# rgb_driver.net
KiCad netlist of a schematic drawn in EAGLE
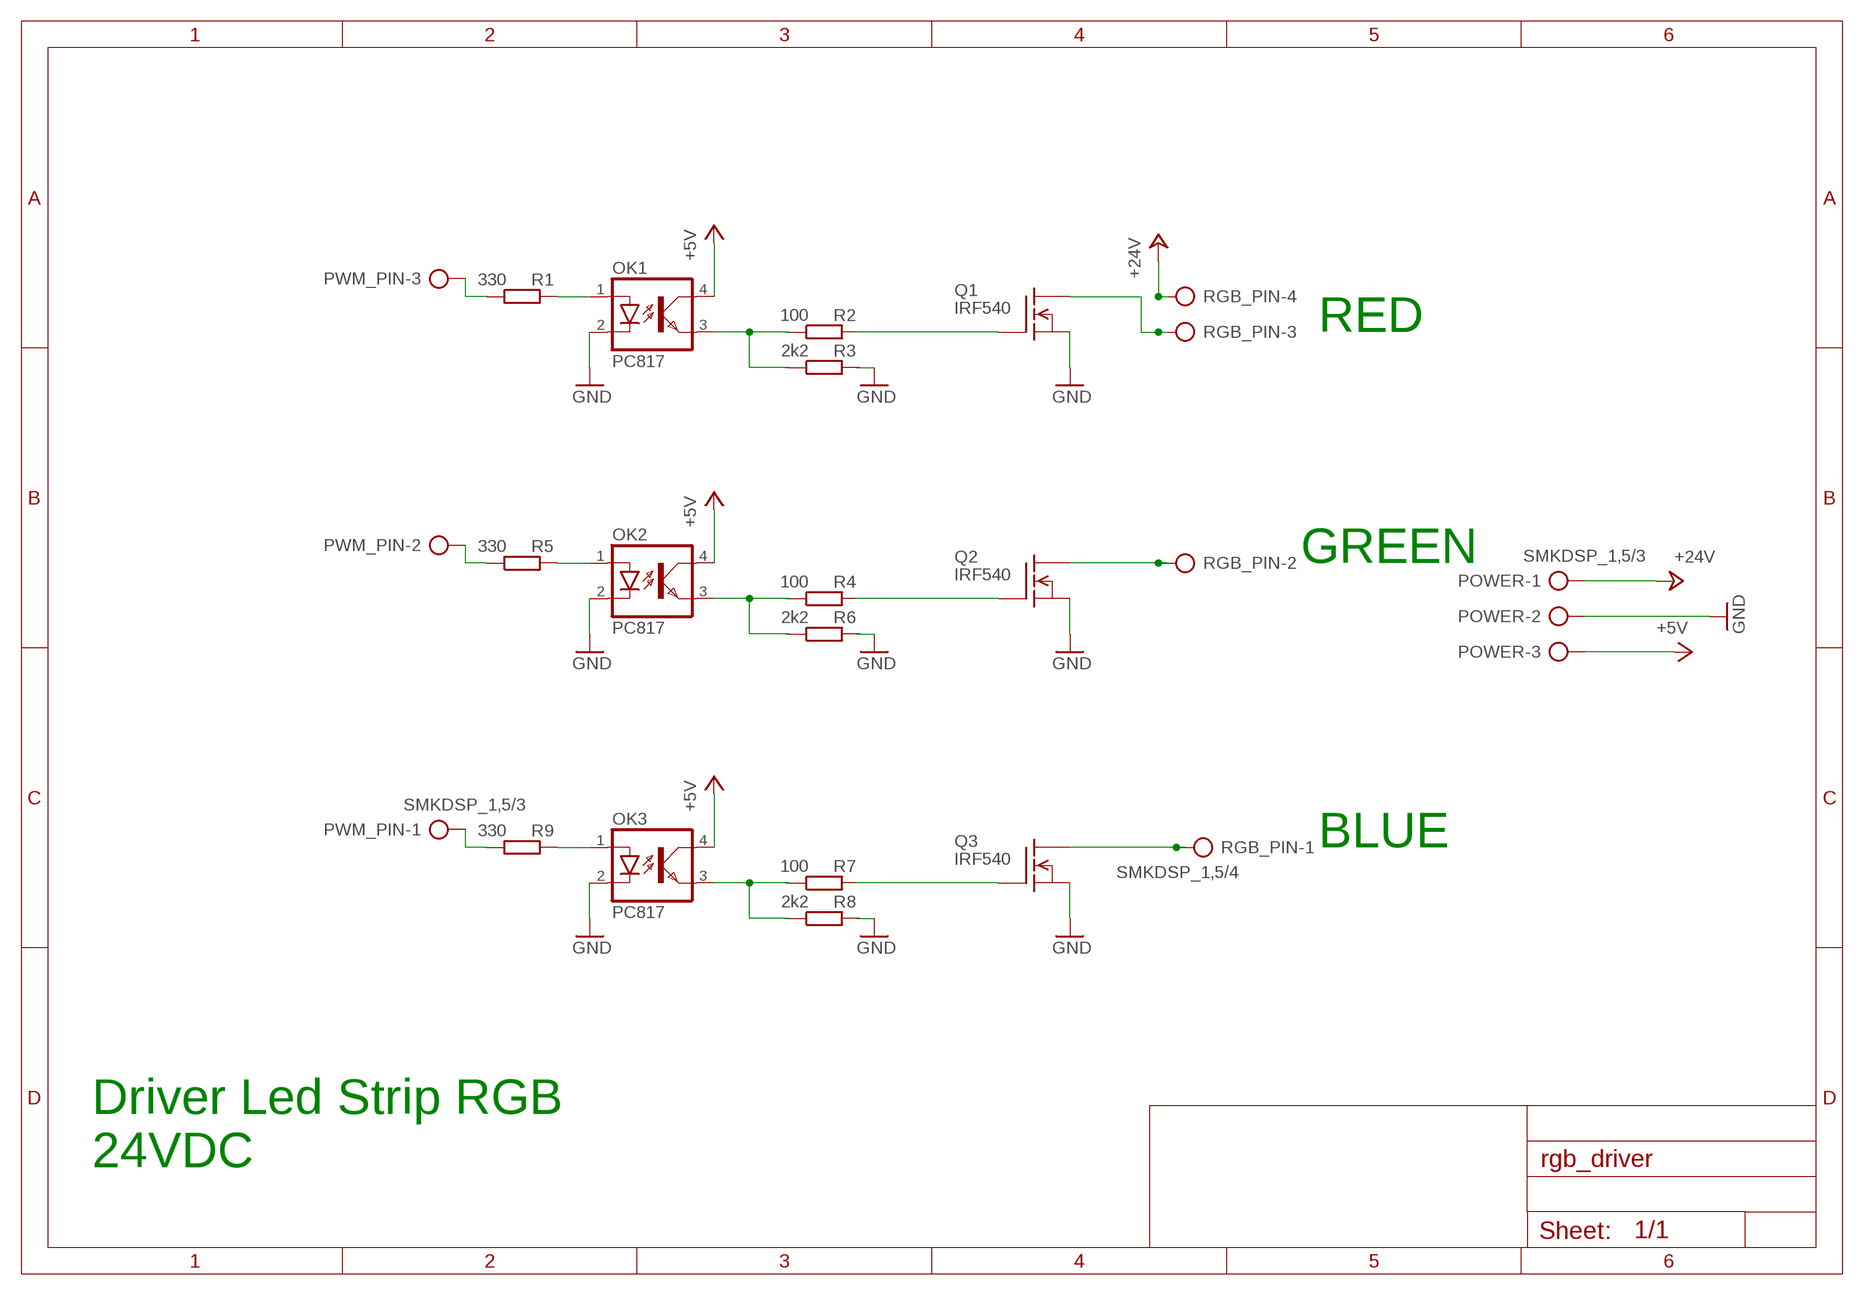
[diagram p0: schematic, sheet 1]

(export (version "E")
  (design (tool "Eeschema 10.0.6"))
  (components
    (comp (ref "OK1")
      (value "PC817")
      (footprint "eagle-import:DIL04")
      (fields (field (name "MPN") "PC817X4J000F"))
      (libsource (lib "eagle-import") (part "PC817"))
    )
    (comp (ref "OK2")
      (value "PC817")
      (footprint "eagle-import:DIL04")
      (fields (field (name "MPN") "PC817X4J000F"))
      (libsource (lib "eagle-import") (part "PC817"))
    )
    (comp (ref "OK3")
      (value "PC817")
      (footprint "eagle-import:DIL04")
      (fields (field (name "MPN") "PC817X4J000F"))
      (libsource (lib "eagle-import") (part "PC817"))
    )
    (comp (ref "POWER")
      (value "SMKDSP_1,5/3")
      (footprint "eagle-import:SMKDSP_1,5_3")
      (fields (field (name "MF") "FARNELL") (field (name "MPN") "1733583"))
      (libsource (lib "eagle-import") (part "SMKDSP_1,5/3"))
    )
    (comp (ref "PWM_PIN")
      (value "SMKDSP_1,5/3")
      (footprint "eagle-import:SMKDSP_1,5_3")
      (fields (field (name "MF") "FARNELL") (field (name "MPN") "1733583"))
      (libsource (lib "eagle-import") (part "SMKDSP_1,5/3"))
    )
    (comp (ref "Q1")
      (value "IRF540")
      (footprint "eagle-import:TO220")
      (libsource (lib "eagle-import") (part "IRF540"))
    )
    (comp (ref "Q2")
      (value "IRF540")
      (footprint "eagle-import:TO220")
      (libsource (lib "eagle-import") (part "IRF540"))
    )
    (comp (ref "Q3")
      (value "IRF540")
      (footprint "eagle-import:TO220")
      (libsource (lib "eagle-import") (part "IRF540"))
    )
    (comp (ref "R1")
      (value "330")
      (footprint "eagle-import:0207_10")
      (libsource (lib "eagle-import") (part "R-EU_0207/10"))
    )
    (comp (ref "R2")
      (value "100")
      (footprint "eagle-import:0207_10")
      (libsource (lib "eagle-import") (part "R-EU_0207/10"))
    )
    (comp (ref "R3")
      (value "2k2")
      (footprint "eagle-import:0207_10")
      (libsource (lib "eagle-import") (part "R-EU_0207/10"))
    )
    (comp (ref "R4")
      (value "100")
      (footprint "eagle-import:0207_10")
      (libsource (lib "eagle-import") (part "R-EU_0207/10"))
    )
    (comp (ref "R5")
      (value "330")
      (footprint "eagle-import:0207_10")
      (libsource (lib "eagle-import") (part "R-EU_0207/10"))
    )
    (comp (ref "R6")
      (value "2k2")
      (footprint "eagle-import:0207_10")
      (libsource (lib "eagle-import") (part "R-EU_0207/10"))
    )
    (comp (ref "R7")
      (value "100")
      (footprint "eagle-import:0207_10")
      (libsource (lib "eagle-import") (part "R-EU_0207/10"))
    )
    (comp (ref "R8")
      (value "2k2")
      (footprint "eagle-import:0207_10")
      (libsource (lib "eagle-import") (part "R-EU_0207/10"))
    )
    (comp (ref "R9")
      (value "330")
      (footprint "eagle-import:0207_10")
      (libsource (lib "eagle-import") (part "R-EU_0207/10"))
    )
    (comp (ref "RGB_PIN")
      (value "SMKDSP_1,5/4")
      (footprint "eagle-import:SMKDSP_1,5_4")
      (fields (field (name "MF") "FARNELL") (field (name "MPN") "1733596"))
      (libsource (lib "eagle-import") (part "SMKDSP_1,5/4"))
    )
  )
  (nets
    (net (code "1") (name "+5V") (class "Default")
      (node (ref "OK1") (pin "4") (pinfunction "COL_4") (pintype "passive"))
      (node (ref "OK2") (pin "4") (pinfunction "COL_4") (pintype "passive"))
      (node (ref "OK3") (pin "4") (pinfunction "COL_4") (pintype "passive"))
      (node (ref "POWER") (pin "3") (pinfunction "KL_3") (pintype "passive"))
    )
    (net (code "2") (name "+24V") (class "Default")
      (node (ref "POWER") (pin "1") (pinfunction "KL_1") (pintype "passive"))
      (node (ref "RGB_PIN") (pin "4") (pinfunction "KL_4") (pintype "passive"))
    )
    (net (code "3") (name "GND") (class "Default")
      (node (ref "OK1") (pin "2") (pinfunction "C_2") (pintype "passive"))
      (node (ref "OK2") (pin "2") (pinfunction "C_2") (pintype "passive"))
      (node (ref "OK3") (pin "2") (pinfunction "C_2") (pintype "passive"))
      (node (ref "POWER") (pin "2") (pinfunction "KL_2") (pintype "passive"))
      (node (ref "Q1") (pin "3") (pinfunction "S_3") (pintype "passive"))
      (node (ref "Q2") (pin "3") (pinfunction "S_3") (pintype "passive"))
      (node (ref "Q3") (pin "3") (pinfunction "S_3") (pintype "passive"))
      (node (ref "R3") (pin "2") (pinfunction "2_2") (pintype "passive"))
      (node (ref "R6") (pin "2") (pinfunction "2_2") (pintype "passive"))
      (node (ref "R8") (pin "2") (pinfunction "2_2") (pintype "passive"))
    )
    (net (code "4") (name "Net-(OK1-A)") (class "Default")
      (node (ref "OK1") (pin "1") (pinfunction "A_1") (pintype "passive"))
      (node (ref "R1") (pin "2") (pinfunction "2_2") (pintype "passive"))
    )
    (net (code "5") (name "Net-(OK1-EMIT)") (class "Default")
      (node (ref "OK1") (pin "3") (pinfunction "EMIT_3") (pintype "passive"))
      (node (ref "R2") (pin "1") (pinfunction "1_1") (pintype "passive"))
      (node (ref "R3") (pin "1") (pinfunction "1_1") (pintype "passive"))
    )
    (net (code "6") (name "Net-(OK2-A)") (class "Default")
      (node (ref "OK2") (pin "1") (pinfunction "A_1") (pintype "passive"))
      (node (ref "R5") (pin "2") (pinfunction "2_2") (pintype "passive"))
    )
    (net (code "7") (name "Net-(OK2-EMIT)") (class "Default")
      (node (ref "OK2") (pin "3") (pinfunction "EMIT_3") (pintype "passive"))
      (node (ref "R4") (pin "1") (pinfunction "1_1") (pintype "passive"))
      (node (ref "R6") (pin "1") (pinfunction "1_1") (pintype "passive"))
    )
    (net (code "8") (name "Net-(OK3-A)") (class "Default")
      (node (ref "OK3") (pin "1") (pinfunction "A_1") (pintype "passive"))
      (node (ref "R9") (pin "2") (pinfunction "2_2") (pintype "passive"))
    )
    (net (code "9") (name "Net-(OK3-EMIT)") (class "Default")
      (node (ref "OK3") (pin "3") (pinfunction "EMIT_3") (pintype "passive"))
      (node (ref "R7") (pin "1") (pinfunction "1_1") (pintype "passive"))
      (node (ref "R8") (pin "1") (pinfunction "1_1") (pintype "passive"))
    )
    (net (code "10") (name "Net-(PWM_PINA-KL)") (class "Default")
      (node (ref "PWM_PIN") (pin "1") (pinfunction "KL_1") (pintype "passive"))
      (node (ref "R9") (pin "1") (pinfunction "1_1") (pintype "passive"))
    )
    (net (code "11") (name "Net-(PWM_PINB-KL)") (class "Default")
      (node (ref "PWM_PIN") (pin "2") (pinfunction "KL_2") (pintype "passive"))
      (node (ref "R5") (pin "1") (pinfunction "1_1") (pintype "passive"))
    )
    (net (code "12") (name "Net-(PWM_PINC-KL)") (class "Default")
      (node (ref "PWM_PIN") (pin "3") (pinfunction "KL_3") (pintype "passive"))
      (node (ref "R1") (pin "1") (pinfunction "1_1") (pintype "passive"))
    )
    (net (code "13") (name "Net-(Q1-D)") (class "Default")
      (node (ref "Q1") (pin "2") (pinfunction "D_2") (pintype "passive"))
      (node (ref "RGB_PIN") (pin "3") (pinfunction "KL_3") (pintype "passive"))
    )
    (net (code "14") (name "Net-(Q1-G)") (class "Default")
      (node (ref "Q1") (pin "1") (pinfunction "G_1") (pintype "passive"))
      (node (ref "R2") (pin "2") (pinfunction "2_2") (pintype "passive"))
    )
    (net (code "15") (name "Net-(Q2-D)") (class "Default")
      (node (ref "Q2") (pin "2") (pinfunction "D_2") (pintype "passive"))
      (node (ref "RGB_PIN") (pin "2") (pinfunction "KL_2") (pintype "passive"))
    )
    (net (code "16") (name "Net-(Q2-G)") (class "Default")
      (node (ref "Q2") (pin "1") (pinfunction "G_1") (pintype "passive"))
      (node (ref "R4") (pin "2") (pinfunction "2_2") (pintype "passive"))
    )
    (net (code "17") (name "Net-(Q3-D)") (class "Default")
      (node (ref "Q3") (pin "2") (pinfunction "D_2") (pintype "passive"))
      (node (ref "RGB_PIN") (pin "1") (pinfunction "KL_1") (pintype "passive"))
    )
    (net (code "18") (name "Net-(Q3-G)") (class "Default")
      (node (ref "Q3") (pin "1") (pinfunction "G_1") (pintype "passive"))
      (node (ref "R7") (pin "2") (pinfunction "2_2") (pintype "passive"))
    )
  )
)
